# Schematic_OpenBook.net
KiCad netlist of a schematic drawn in EAGLE
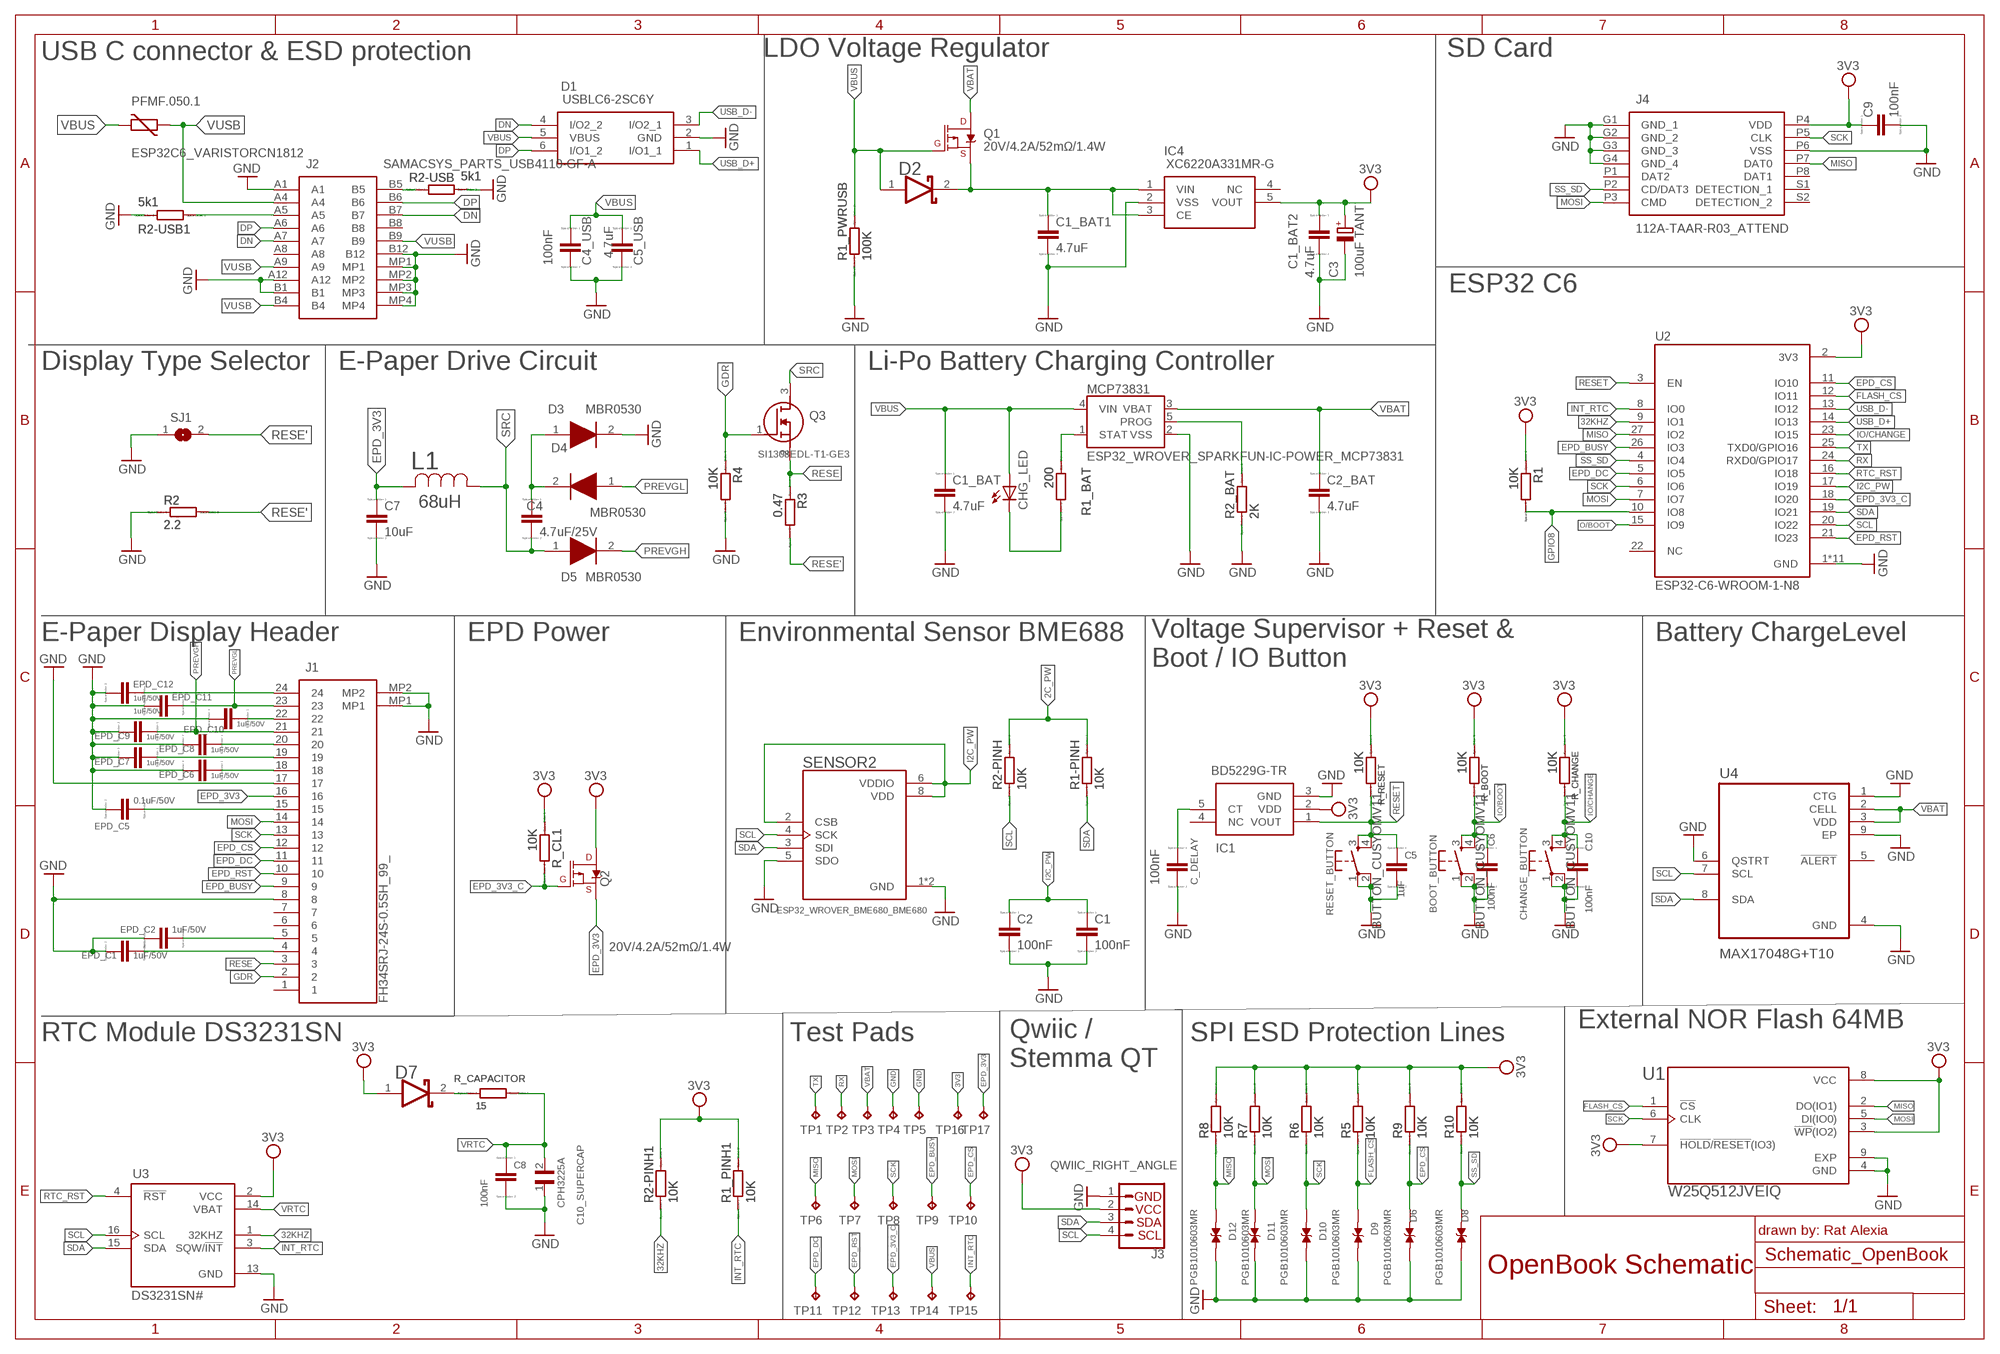
[diagram p0: schematic, sheet 1]

(export (version "E")
  (design (tool "Eeschema 10.0.6"))
  (components
    (comp (ref "BOOT_BUTTON")
      (value "BUTTON_CUSYOMV11")
      (footprint "eagle-import:MYBUTTON")
      (libsource (lib "eagle-import") (part "BUTTON_CUSYOMV11"))
    )
    (comp (ref "C1")
      (value "100nF")
      (footprint "eagle-import:ESP32_WROVER_EAGLE-LTSPICE_C0402")
      (libsource (lib "eagle-import") (part "ESP32_WROVER_EAGLE-LTSPICE_C1"))
    )
    (comp (ref "C1_BAT")
      (value "4.7uF")
      (footprint "eagle-import:ESP32_WROVER_EAGLE-LTSPICE_C0402")
      (libsource (lib "eagle-import") (part "ESP32_WROVER_EAGLE-LTSPICE_C1"))
    )
    (comp (ref "C1_BAT1")
      (value "4.7uF")
      (footprint "eagle-import:ESP32_WROVER_EAGLE-LTSPICE_C0402")
      (libsource (lib "eagle-import") (part "ESP32_WROVER_EAGLE-LTSPICE_C1"))
    )
    (comp (ref "C1_BAT2")
      (value "4.7uF")
      (footprint "eagle-import:ESP32_WROVER_EAGLE-LTSPICE_C0402")
      (libsource (lib "eagle-import") (part "ESP32_WROVER_EAGLE-LTSPICE_C1"))
    )
    (comp (ref "C2")
      (value "100nF")
      (footprint "eagle-import:ESP32_WROVER_EAGLE-LTSPICE_C0402")
      (libsource (lib "eagle-import") (part "ESP32_WROVER_EAGLE-LTSPICE_C1"))
    )
    (comp (ref "C2_BAT")
      (value "4.7uF")
      (footprint "eagle-import:ESP32_WROVER_EAGLE-LTSPICE_C0402")
      (libsource (lib "eagle-import") (part "ESP32_WROVER_EAGLE-LTSPICE_C1"))
    )
    (comp (ref "C3")
      (value "100uF TANT")
      (footprint "eagle-import:RCL_CT3528")
      (libsource (lib "eagle-import") (part "RCL_CPOL-EUCT3528"))
    )
    (comp (ref "C4")
      (value "4.7uF/25V")
      (footprint "eagle-import:ESP32_WROVER_EAGLE-LTSPICE_C0402")
      (libsource (lib "eagle-import") (part "ESP32_WROVER_EAGLE-LTSPICE_C1"))
    )
    (comp (ref "C4_USB")
      (value "100nF")
      (footprint "eagle-import:ESP32_WROVER_EAGLE-LTSPICE_C0402")
      (libsource (lib "eagle-import") (part "ESP32_WROVER_EAGLE-LTSPICE_C1"))
    )
    (comp (ref "C5")
      (value "1uF")
      (footprint "eagle-import:ESP32_WROVER_EAGLE-LTSPICE_C0402")
      (libsource (lib "eagle-import") (part "ESP32_WROVER_EAGLE-LTSPICE_C1"))
    )
    (comp (ref "C5_USB")
      (value "4.7uF")
      (footprint "eagle-import:ESP32_WROVER_EAGLE-LTSPICE_C0402")
      (libsource (lib "eagle-import") (part "ESP32_WROVER_EAGLE-LTSPICE_C1"))
    )
    (comp (ref "C6")
      (value "100nF")
      (footprint "eagle-import:ESP32_WROVER_EAGLE-LTSPICE_C0402")
      (libsource (lib "eagle-import") (part "ESP32_WROVER_EAGLE-LTSPICE_C1"))
    )
    (comp (ref "C7")
      (value "10uF")
      (footprint "eagle-import:ESP32_WROVER_EAGLE-LTSPICE_C0402")
      (libsource (lib "eagle-import") (part "ESP32_WROVER_EAGLE-LTSPICE_C1"))
    )
    (comp (ref "C8")
      (value "100nF")
      (footprint "eagle-import:ESP32_WROVER_EAGLE-LTSPICE_C0402")
      (libsource (lib "eagle-import") (part "ESP32_WROVER_EAGLE-LTSPICE_C1"))
    )
    (comp (ref "C9")
      (value "100nF")
      (footprint "eagle-import:ESP32_WROVER_EAGLE-LTSPICE_C0402")
      (libsource (lib "eagle-import") (part "ESP32_WROVER_EAGLE-LTSPICE_C1"))
    )
    (comp (ref "C10")
      (value "100nF")
      (footprint "eagle-import:ESP32_WROVER_EAGLE-LTSPICE_C0402")
      (libsource (lib "eagle-import") (part "ESP32_WROVER_EAGLE-LTSPICE_C1"))
    )
    (comp (ref "C10_SUPERCAP")
      (value "CPH3225A")
      (footprint "eagle-import:CAPCP3225X100N")
      (fields (field (name "MF") "Seiko Instruments"))
      (libsource (lib "eagle-import") (part "CPH3225A"))
    )
    (comp (ref "CHANGE_BUTTON")
      (value "BUTTON_CUSYOMV11")
      (footprint "eagle-import:MYBUTTON")
      (libsource (lib "eagle-import") (part "BUTTON_CUSYOMV11"))
    )
    (comp (ref "CHG_LED")
      (value "ADAFRUIT_LEDCHIP-LED0603")
      (footprint "eagle-import:ADAFRUIT_CHIP-LED0603")
      (libsource (lib "eagle-import") (part "ADAFRUIT_LEDCHIP-LED0603"))
    )
    (comp (ref "C_DELAY")
      (value "100nF")
      (footprint "eagle-import:ESP32_WROVER_EAGLE-LTSPICE_C0402")
      (libsource (lib "eagle-import") (part "ESP32_WROVER_EAGLE-LTSPICE_C1"))
    )
    (comp (ref "D1")
      (value "USBLC6-2SC6Y")
      (footprint "eagle-import:SOT95P280X145-6N")
      (fields (field (name "MF") "STMicroelectronics"))
      (libsource (lib "eagle-import") (part "USBLC6-2SC6Y"))
    )
    (comp (ref "D2")
      (value "ESP32_WROVER_AVX---SD0805S020S1R0_AVX_SD0805S020S1R0_0_01")
      (footprint "eagle-import:ESP32_WROVER_AVX---SD0805S020S1R0_AVX_SD0805S020S1R0_0")
      (libsource (lib "eagle-import") (part "ESP32_WROVER_AVX---SD0805S020S1R0_AVX_SD0805S020S1R0_0_01"))
    )
    (comp (ref "D3")
      (value "MBR0530")
      (footprint "eagle-import:SOD3716X135N")
      (libsource (lib "eagle-import") (part "MBR0530"))
    )
    (comp (ref "D4")
      (value "MBR0530")
      (footprint "eagle-import:SOD3716X135N")
      (libsource (lib "eagle-import") (part "MBR0530"))
    )
    (comp (ref "D5")
      (value "MBR0530")
      (footprint "eagle-import:SOD3716X135N")
      (libsource (lib "eagle-import") (part "MBR0530"))
    )
    (comp (ref "D6")
      (value "PGB1010603MR")
      (footprint "eagle-import:DIOC1608X36N")
      (libsource (lib "eagle-import") (part "PGB1010603MR"))
    )
    (comp (ref "D7")
      (value "ESP32_WROVER_AVX---SD0805S020S1R0_AVX_SD0805S020S1R0_0_01")
      (footprint "eagle-import:ESP32_WROVER_AVX---SD0805S020S1R0_AVX_SD0805S020S1R0_0")
      (libsource (lib "eagle-import") (part "ESP32_WROVER_AVX---SD0805S020S1R0_AVX_SD0805S020S1R0_0_01"))
    )
    (comp (ref "D8")
      (value "PGB1010603MR")
      (footprint "eagle-import:DIOC1608X36N")
      (libsource (lib "eagle-import") (part "PGB1010603MR"))
    )
    (comp (ref "D9")
      (value "PGB1010603MR")
      (footprint "eagle-import:DIOC1608X36N")
      (libsource (lib "eagle-import") (part "PGB1010603MR"))
    )
    (comp (ref "D10")
      (value "PGB1010603MR")
      (footprint "eagle-import:DIOC1608X36N")
      (libsource (lib "eagle-import") (part "PGB1010603MR"))
    )
    (comp (ref "D11")
      (value "PGB1010603MR")
      (footprint "eagle-import:DIOC1608X36N")
      (libsource (lib "eagle-import") (part "PGB1010603MR"))
    )
    (comp (ref "D12")
      (value "PGB1010603MR")
      (footprint "eagle-import:DIOC1608X36N")
      (libsource (lib "eagle-import") (part "PGB1010603MR"))
    )
    (comp (ref "EPD_C1")
      (value "1uF/50V")
      (footprint "eagle-import:ESP32_WROVER_EAGLE-LTSPICE_C0402")
      (libsource (lib "eagle-import") (part "ESP32_WROVER_EAGLE-LTSPICE_C1"))
    )
    (comp (ref "EPD_C2")
      (value "1uF/50V")
      (footprint "eagle-import:ESP32_WROVER_EAGLE-LTSPICE_C0402")
      (libsource (lib "eagle-import") (part "ESP32_WROVER_EAGLE-LTSPICE_C1"))
    )
    (comp (ref "EPD_C5")
      (value "0.1uF/50V")
      (footprint "eagle-import:ESP32_WROVER_EAGLE-LTSPICE_C0402")
      (libsource (lib "eagle-import") (part "ESP32_WROVER_EAGLE-LTSPICE_C1"))
    )
    (comp (ref "EPD_C6")
      (value "1uF/50V")
      (footprint "eagle-import:ESP32_WROVER_EAGLE-LTSPICE_C0402")
      (libsource (lib "eagle-import") (part "ESP32_WROVER_EAGLE-LTSPICE_C1"))
    )
    (comp (ref "EPD_C7")
      (value "1uF/50V")
      (footprint "eagle-import:ESP32_WROVER_EAGLE-LTSPICE_C0402")
      (libsource (lib "eagle-import") (part "ESP32_WROVER_EAGLE-LTSPICE_C1"))
    )
    (comp (ref "EPD_C8")
      (value "1uF/50V")
      (footprint "eagle-import:ESP32_WROVER_EAGLE-LTSPICE_C0402")
      (libsource (lib "eagle-import") (part "ESP32_WROVER_EAGLE-LTSPICE_C1"))
    )
    (comp (ref "EPD_C9")
      (value "1uF/50V")
      (footprint "eagle-import:ESP32_WROVER_EAGLE-LTSPICE_C0402")
      (libsource (lib "eagle-import") (part "ESP32_WROVER_EAGLE-LTSPICE_C1"))
    )
    (comp (ref "EPD_C10")
      (value "1uF/50V")
      (footprint "eagle-import:ESP32_WROVER_EAGLE-LTSPICE_C0402")
      (libsource (lib "eagle-import") (part "ESP32_WROVER_EAGLE-LTSPICE_C1"))
    )
    (comp (ref "EPD_C11")
      (value "1uF/50V")
      (footprint "eagle-import:ESP32_WROVER_EAGLE-LTSPICE_C0402")
      (libsource (lib "eagle-import") (part "ESP32_WROVER_EAGLE-LTSPICE_C1"))
    )
    (comp (ref "EPD_C12")
      (value "1uF/50V")
      (footprint "eagle-import:ESP32_WROVER_EAGLE-LTSPICE_C0402")
      (libsource (lib "eagle-import") (part "ESP32_WROVER_EAGLE-LTSPICE_C1"))
    )
    (comp (ref "IC1")
      (value "BD5229G-TR")
      (footprint "eagle-import:SOT95P280X125-5N")
      (fields (field (name "MOUSER_PART_NUMBER") "755-BD5229G-TR"))
      (libsource (lib "eagle-import") (part "BD5229G-TR"))
    )
    (comp (ref "IC4")
      (value "XC6220A331MR-G")
      (footprint "eagle-import:SOT95P280X120-5N")
      (fields (field (name "MOUSER_PART_NUMBER") "865-XC6220A331MR-G"))
      (libsource (lib "eagle-import") (part "XC6220A331MR-G"))
    )
    (comp (ref "J1")
      (value "FH34SRJ-24S-0.5SH_99_")
      (footprint "eagle-import:FH34SRJ24S05SH99")
      (fields
        (field (name "MANUFACTURER_PART_NUMBER") "FH34SRJ-24S-0.5SH(99)")
        (field (name "MOUSER_PART_NUMBER") "798-FH34SRJ24S05SH99")
      )
      (libsource (lib "eagle-import") (part "FH34SRJ-24S-0.5SH_99_"))
    )
    (comp (ref "J2")
      (value "SAMACSYS_PARTS_USB4110-GF-A")
      (footprint "eagle-import:SAMACSYS_PARTS_USB4110GFA")
      (fields
        (field (name "MANUFACTURER_PART_NUMBER") "USB4110-GF-A")
        (field (name "MOUSER_PART_NUMBER") "640-USB4110-GF-A")
      )
      (libsource (lib "eagle-import") (part "SAMACSYS_PARTS_USB4110-GF-A"))
    )
    (comp (ref "J3")
      (value "QWIIC_RIGHT_ANGLE")
      (footprint "eagle-import:JST04_1MM_RA")
      (libsource (lib "eagle-import") (part "QWIIC_CONNECTORJS-1MM"))
    )
    (comp (ref "J4")
      (value "112A-TAAR-R03_ATTEND")
      (footprint "eagle-import:112ATAARR03ATTEND")
      (fields (field (name "MANUFACTURER_PART_NUMBER") "112A-TAAR-R03 ATTEND"))
      (libsource (lib "eagle-import") (part "112A-TAAR-R03_ATTEND"))
    )
    (comp (ref "L1")
      (value "68uH")
      (footprint "eagle-import:IND_4828-WE-TPC_WRE")
      (fields
        (field (name "MANUFACTURER_PART_NUMBER") "744043680")
        (field (name "COPYRIGHT") "Copyright (C) 2024 Ultra Librarian. All rights reserved.")
      )
      (libsource (lib "eagle-import") (part "744043680IND_4828-WE-TPC_WRE"))
    )
    (comp (ref "MCP73831")
      (value "ESP32_WROVER_SPARKFUN-IC-POWER_MCP73831")
      (footprint "eagle-import:ESP32_WROVER_SPARKFUN-IC-POWER_SOT23-5")
      (libsource (lib "eagle-import") (part "ESP32_WROVER_SPARKFUN-IC-POWER_MCP73831"))
    )
    (comp (ref "PFMF.050.1")
      (value "ESP32C6_VARISTORCN1812")
      (footprint "eagle-import:ESP32C6_VARISTOR_CT_CN1812")
      (libsource (lib "eagle-import") (part "ESP32C6_VARISTORCN1812"))
    )
    (comp (ref "Q1")
      (value "20V/4.2A/52mΩ/1.4W")
      (footprint "eagle-import:ESP32_WROVER_SPARKFUN-DISCRETESEMI_SOT23-3")
      (libsource (lib "eagle-import") (part "ESP32_WROVER_SPARKFUN-DISCRETESEMI_MOSFET_PCH1"))
    )
    (comp (ref "Q2")
      (value "20V/4.2A/52mΩ/1.4W")
      (footprint "eagle-import:ESP32_WROVER_SPARKFUN-DISCRETESEMI_SOT23-3")
      (libsource (lib "eagle-import") (part "ESP32_WROVER_SPARKFUN-DISCRETESEMI_MOSFET_PCH1"))
    )
    (comp (ref "Q3")
      (value "SI1308EDL-T1-GE3")
      (footprint "eagle-import:SOT65P210X110-3N")
      (fields (field (name "MF") "Vishay Siliconix"))
      (libsource (lib "eagle-import") (part "SI1308EDL-T1-GE3"))
    )
    (comp (ref "R1")
      (value "10K")
      (footprint "eagle-import:ESP32_WROVER_EAGLE-LTSPICE_C0402")
      (libsource (lib "eagle-import") (part "ESP32_WROVER_EAGLE-LTSPICE_R"))
    )
    (comp (ref "R1-PINH")
      (value "10K")
      (footprint "eagle-import:ESP32_WROVER_EAGLE-LTSPICE_C0402")
      (libsource (lib "eagle-import") (part "ESP32_WROVER_EAGLE-LTSPICE_R"))
    )
    (comp (ref "R1_BAT")
      (value "200")
      (footprint "eagle-import:ESP32_WROVER_EAGLE-LTSPICE_C0402")
      (libsource (lib "eagle-import") (part "ESP32_WROVER_EAGLE-LTSPICE_R"))
    )
    (comp (ref "R1_PINH1")
      (value "10K")
      (footprint "eagle-import:ESP32_WROVER_EAGLE-LTSPICE_C0402")
      (libsource (lib "eagle-import") (part "ESP32_WROVER_EAGLE-LTSPICE_R"))
    )
    (comp (ref "R1_PWRUSB")
      (value "100K")
      (footprint "eagle-import:ESP32_WROVER_EAGLE-LTSPICE_C0402")
      (libsource (lib "eagle-import") (part "ESP32_WROVER_EAGLE-LTSPICE_R"))
    )
    (comp (ref "R2")
      (value "2.2")
      (footprint "eagle-import:ESP32_WROVER_EAGLE-LTSPICE_C0402")
      (libsource (lib "eagle-import") (part "ESP32_WROVER_EAGLE-LTSPICE_R"))
    )
    (comp (ref "R2-PINH")
      (value "10K")
      (footprint "eagle-import:ESP32_WROVER_EAGLE-LTSPICE_C0402")
      (libsource (lib "eagle-import") (part "ESP32_WROVER_EAGLE-LTSPICE_R"))
    )
    (comp (ref "R2-PINH1")
      (value "10K")
      (footprint "eagle-import:ESP32_WROVER_EAGLE-LTSPICE_C0402")
      (libsource (lib "eagle-import") (part "ESP32_WROVER_EAGLE-LTSPICE_R"))
    )
    (comp (ref "R2-USB")
      (value "5k1")
      (footprint "eagle-import:ESP32_WROVER_EAGLE-LTSPICE_C0402")
      (libsource (lib "eagle-import") (part "ESP32_WROVER_EAGLE-LTSPICE_R"))
    )
    (comp (ref "R2-USB1")
      (value "5k1")
      (footprint "eagle-import:ESP32_WROVER_EAGLE-LTSPICE_C0402")
      (libsource (lib "eagle-import") (part "ESP32_WROVER_EAGLE-LTSPICE_R"))
    )
    (comp (ref "R2_BAT")
      (value "2K")
      (footprint "eagle-import:ESP32_WROVER_EAGLE-LTSPICE_C0402")
      (libsource (lib "eagle-import") (part "ESP32_WROVER_EAGLE-LTSPICE_R"))
    )
    (comp (ref "R3")
      (value "0.47")
      (footprint "eagle-import:ESP32_WROVER_EAGLE-LTSPICE_C0402")
      (libsource (lib "eagle-import") (part "ESP32_WROVER_EAGLE-LTSPICE_R"))
    )
    (comp (ref "R4")
      (value "10K")
      (footprint "eagle-import:ESP32_WROVER_EAGLE-LTSPICE_C0402")
      (libsource (lib "eagle-import") (part "ESP32_WROVER_EAGLE-LTSPICE_R"))
    )
    (comp (ref "R5")
      (value "10K")
      (footprint "eagle-import:ESP32_WROVER_EAGLE-LTSPICE_C0402")
      (libsource (lib "eagle-import") (part "ESP32_WROVER_EAGLE-LTSPICE_R"))
    )
    (comp (ref "R6")
      (value "10K")
      (footprint "eagle-import:ESP32_WROVER_EAGLE-LTSPICE_C0402")
      (libsource (lib "eagle-import") (part "ESP32_WROVER_EAGLE-LTSPICE_R"))
    )
    (comp (ref "R7")
      (value "10K")
      (footprint "eagle-import:ESP32_WROVER_EAGLE-LTSPICE_C0402")
      (libsource (lib "eagle-import") (part "ESP32_WROVER_EAGLE-LTSPICE_R"))
    )
    (comp (ref "R8")
      (value "10K")
      (footprint "eagle-import:ESP32_WROVER_EAGLE-LTSPICE_C0402")
      (libsource (lib "eagle-import") (part "ESP32_WROVER_EAGLE-LTSPICE_R"))
    )
    (comp (ref "R9")
      (value "10K")
      (footprint "eagle-import:ESP32_WROVER_EAGLE-LTSPICE_C0402")
      (libsource (lib "eagle-import") (part "ESP32_WROVER_EAGLE-LTSPICE_R"))
    )
    (comp (ref "R10")
      (value "10K")
      (footprint "eagle-import:ESP32_WROVER_EAGLE-LTSPICE_C0402")
      (libsource (lib "eagle-import") (part "ESP32_WROVER_EAGLE-LTSPICE_R"))
    )
    (comp (ref "RESET_BUTTON")
      (value "BUTTON_CUSYOMV11")
      (footprint "eagle-import:MYBUTTON")
      (libsource (lib "eagle-import") (part "BUTTON_CUSYOMV11"))
    )
    (comp (ref "R_BOOT")
      (value "10K")
      (footprint "eagle-import:ESP32_WROVER_EAGLE-LTSPICE_C0402")
      (libsource (lib "eagle-import") (part "ESP32_WROVER_EAGLE-LTSPICE_R"))
    )
    (comp (ref "R_CAPACITOR")
      (value "15")
      (footprint "eagle-import:ESP32_WROVER_EAGLE-LTSPICE_C0402")
      (libsource (lib "eagle-import") (part "ESP32_WROVER_EAGLE-LTSPICE_R"))
    )
    (comp (ref "R_CHANGE")
      (value "10K")
      (footprint "eagle-import:ESP32_WROVER_EAGLE-LTSPICE_C0402")
      (libsource (lib "eagle-import") (part "ESP32_WROVER_EAGLE-LTSPICE_R"))
    )
    (comp (ref "R_CL1")
      (value "10K")
      (footprint "eagle-import:ESP32_WROVER_EAGLE-LTSPICE_C0402")
      (libsource (lib "eagle-import") (part "ESP32_WROVER_EAGLE-LTSPICE_R"))
    )
    (comp (ref "R_RESET")
      (value "10K")
      (footprint "eagle-import:ESP32_WROVER_EAGLE-LTSPICE_C0402")
      (libsource (lib "eagle-import") (part "ESP32_WROVER_EAGLE-LTSPICE_R"))
    )
    (comp (ref "SENSOR2")
      (value "ESP32_WROVER_BME680_BME680")
      (footprint "eagle-import:ESP32_WROVER_BME680_PSON80P300X300X100-8N")
      (fields (field (name "MF") "Bosch Sensortec") (field (name "MP") "BME680"))
      (libsource (lib "eagle-import") (part "ESP32_WROVER_BME680_BME680"))
    )
    (comp (ref "SJ1") (value "SJ") (footprint "eagle-import:SJ") (libsource (lib "eagle-import") (part "SJ")))
    (comp (ref "TP1")
      (value "TP1")
      (footprint "eagle-import:TP20R")
      (libsource (lib "eagle-import") (part "TP1"))
    )
    (comp (ref "TP2")
      (value "TP1")
      (footprint "eagle-import:TP20R")
      (libsource (lib "eagle-import") (part "TP1"))
    )
    (comp (ref "TP3")
      (value "TP1")
      (footprint "eagle-import:TP20R")
      (libsource (lib "eagle-import") (part "TP1"))
    )
    (comp (ref "TP4")
      (value "TP1")
      (footprint "eagle-import:TP20R")
      (libsource (lib "eagle-import") (part "TP1"))
    )
    (comp (ref "TP5")
      (value "TP1")
      (footprint "eagle-import:TP20R")
      (libsource (lib "eagle-import") (part "TP1"))
    )
    (comp (ref "TP6")
      (value "TP1")
      (footprint "eagle-import:TP20R")
      (libsource (lib "eagle-import") (part "TP1"))
    )
    (comp (ref "TP7")
      (value "TP1")
      (footprint "eagle-import:TP20R")
      (libsource (lib "eagle-import") (part "TP1"))
    )
    (comp (ref "TP8")
      (value "TP1")
      (footprint "eagle-import:TP20R")
      (libsource (lib "eagle-import") (part "TP1"))
    )
    (comp (ref "TP9")
      (value "TP1")
      (footprint "eagle-import:TP20R")
      (libsource (lib "eagle-import") (part "TP1"))
    )
    (comp (ref "TP10")
      (value "TP1")
      (footprint "eagle-import:TP20R")
      (libsource (lib "eagle-import") (part "TP1"))
    )
    (comp (ref "TP11")
      (value "TP1")
      (footprint "eagle-import:TP20R")
      (libsource (lib "eagle-import") (part "TP1"))
    )
    (comp (ref "TP12")
      (value "TP1")
      (footprint "eagle-import:TP20R")
      (libsource (lib "eagle-import") (part "TP1"))
    )
    (comp (ref "TP13")
      (value "TP1")
      (footprint "eagle-import:TP20R")
      (libsource (lib "eagle-import") (part "TP1"))
    )
    (comp (ref "TP14")
      (value "TP1")
      (footprint "eagle-import:TP20R")
      (libsource (lib "eagle-import") (part "TP1"))
    )
    (comp (ref "TP15")
      (value "TP1")
      (footprint "eagle-import:TP20R")
      (libsource (lib "eagle-import") (part "TP1"))
    )
    (comp (ref "TP16")
      (value "TP1")
      (footprint "eagle-import:TP20R")
      (libsource (lib "eagle-import") (part "TP1"))
    )
    (comp (ref "TP17")
      (value "TP1")
      (footprint "eagle-import:TP20R")
      (libsource (lib "eagle-import") (part "TP1"))
    )
    (comp (ref "U1")
      (value "W25Q512JVEIQ")
      (footprint "eagle-import:SON127P600X800X80-9N")
      (fields (field (name "MF") "Winbond Electronics"))
      (libsource (lib "eagle-import") (part "W25Q512JVEIQ"))
    )
    (comp (ref "U2")
      (value "ESP32-C6-WROOM-1-N8")
      (footprint "eagle-import:XCVR_ESP32-C6-WROOM-1-N8")
      (fields (field (name "MF") "Espressif Systems"))
      (libsource (lib "eagle-import") (part "ESP32-C6-WROOM-1-N8"))
    )
    (comp (ref "U3")
      (value "DS3231SN#")
      (footprint "eagle-import:SOIC127P1032X265-16N")
      (fields (field (name "MF") "Analog Devices"))
      (libsource (lib "eagle-import") (part "DS3231SN#"))
    )
    (comp (ref "U4")
      (value "MAX17048G+T10")
      (footprint "eagle-import:SON50P200X200X80-9N")
      (fields (field (name "MF") "Analog Devices"))
      (libsource (lib "eagle-import") (part "MAX17048G+T10"))
    )
  )
  (nets
    (net (code "1") (name "2C_PW") (class "Default")
      (node (ref "R1-PINH") (pin "2") (pinfunction "2_2") (pintype "passive"))
      (node (ref "R2-PINH") (pin "2") (pinfunction "2_2") (pintype "passive"))
    )
    (net (code "2") (name "3V3") (class "Default")
      (node (ref "C1_BAT2") (pin "1") (pinfunction "1_1") (pintype "passive"))
      (node (ref "C3") (pin "+") (pinfunction "+_+") (pintype "passive"))
      (node (ref "C9") (pin "1") (pinfunction "1_1") (pintype "passive"))
      (node (ref "D7") (pin "1") (pinfunction "ANODE_1") (pintype "bidirectional"))
      (node (ref "IC1") (pin "2") (pinfunction "VDD_2") (pintype "bidirectional"))
      (node (ref "IC4") (pin "5") (pinfunction "VOUT_5") (pintype "bidirectional"))
      (node (ref "J3") (pin "2") (pinfunction "2_2") (pintype "power_in"))
      (node (ref "J4") (pin "P4") (pinfunction "VDD_P4") (pintype "bidirectional"))
      (node (ref "Q2") (pin "1") (pinfunction "D_1") (pintype "bidirectional"))
      (node (ref "R1") (pin "1") (pinfunction "1_1") (pintype "passive"))
      (node (ref "R10") (pin "2") (pinfunction "2_2") (pintype "passive"))
      (node (ref "R1_PINH1") (pin "2") (pinfunction "2_2") (pintype "passive"))
      (node (ref "R2-PINH1") (pin "2") (pinfunction "2_2") (pintype "passive"))
      (node (ref "R5") (pin "2") (pinfunction "2_2") (pintype "passive"))
      (node (ref "R6") (pin "2") (pinfunction "2_2") (pintype "passive"))
      (node (ref "R7") (pin "2") (pinfunction "2_2") (pintype "passive"))
      (node (ref "R8") (pin "2") (pinfunction "2_2") (pintype "passive"))
      (node (ref "R9") (pin "2") (pinfunction "2_2") (pintype "passive"))
      (node (ref "R_BOOT") (pin "1") (pinfunction "1_1") (pintype "passive"))
      (node (ref "R_CHANGE") (pin "1") (pinfunction "1_1") (pintype "passive"))
      (node (ref "R_CL1") (pin "1") (pinfunction "1_1") (pintype "passive"))
      (node (ref "R_RESET") (pin "1") (pinfunction "1_1") (pintype "passive"))
      (node (ref "TP16") (pin "TP") (pinfunction "TP_TP") (pintype "input"))
      (node (ref "U1") (pin "3") (pinfunction "~{WP}(IO2)_3") (pintype "bidirectional"))
      (node (ref "U1") (pin "7") (pinfunction "~{HOLD}/~{RESET}(IO3)_7") (pintype "bidirectional"))
      (node (ref "U1") (pin "8") (pinfunction "VCC_8") (pintype "power_in"))
      (node (ref "U2") (pin "2") (pinfunction "3V3_2") (pintype "power_in"))
      (node (ref "U3") (pin "2") (pinfunction "VCC_2") (pintype "power_in"))
    )
    (net (code "3") (name "32KHZ") (class "Default")
      (node (ref "R2-PINH1") (pin "1") (pinfunction "1_1") (pintype "passive"))
      (node (ref "U2") (pin "9") (pinfunction "IO1_9") (pintype "bidirectional"))
      (node (ref "U3") (pin "1") (pinfunction "32KHZ_1") (pintype "output"))
    )
    (net (code "4") (name "DN") (class "Default")
      (node (ref "D1") (pin "4") (pinfunction "I/O2_2_4") (pintype "bidirectional"))
      (node (ref "J2") (pin "A7") (pinfunction "A7_A7") (pintype "bidirectional"))
      (node (ref "J2") (pin "B7") (pinfunction "B7_B7") (pintype "bidirectional"))
    )
    (net (code "5") (name "DP") (class "Default")
      (node (ref "D1") (pin "6") (pinfunction "I/O1_2_6") (pintype "bidirectional"))
      (node (ref "J2") (pin "A6") (pinfunction "A6_A6") (pintype "bidirectional"))
      (node (ref "J2") (pin "B6") (pinfunction "B6_B6") (pintype "bidirectional"))
    )
    (net (code "6") (name "EPD_3V3") (class "Default")
      (node (ref "C7") (pin "1") (pinfunction "1_1") (pintype "passive"))
      (node (ref "J1") (pin "16") (pinfunction "16_16") (pintype "bidirectional"))
      (node (ref "L1") (pin "2") (pinfunction "2_2") (pintype "passive"))
      (node (ref "Q2") (pin "3") (pinfunction "S_3") (pintype "bidirectional"))
      (node (ref "TP17") (pin "TP") (pinfunction "TP_TP") (pintype "input"))
    )
    (net (code "7") (name "EPD_3V3_C") (class "Default")
      (node (ref "Q2") (pin "2") (pinfunction "G_2") (pintype "bidirectional"))
      (node (ref "R_CL1") (pin "2") (pinfunction "2_2") (pintype "passive"))
      (node (ref "TP13") (pin "TP") (pinfunction "TP_TP") (pintype "input"))
      (node (ref "U2") (pin "18") (pinfunction "IO20_18") (pintype "bidirectional"))
    )
    (net (code "8") (name "EPD_BUSY") (class "Default")
      (node (ref "J1") (pin "9") (pinfunction "9_9") (pintype "bidirectional"))
      (node (ref "TP9") (pin "TP") (pinfunction "TP_TP") (pintype "input"))
      (node (ref "U2") (pin "26") (pinfunction "IO3_26") (pintype "bidirectional"))
    )
    (net (code "9") (name "EPD_CS") (class "Default")
      (node (ref "D6") (pin "1") (pinfunction "1_1") (pintype "passive"))
      (node (ref "J1") (pin "12") (pinfunction "12_12") (pintype "bidirectional"))
      (node (ref "R9") (pin "1") (pinfunction "1_1") (pintype "passive"))
      (node (ref "TP10") (pin "TP") (pinfunction "TP_TP") (pintype "input"))
      (node (ref "U2") (pin "11") (pinfunction "IO10_11") (pintype "bidirectional"))
    )
    (net (code "10") (name "EPD_DC") (class "Default")
      (node (ref "J1") (pin "11") (pinfunction "11_11") (pintype "bidirectional"))
      (node (ref "TP11") (pin "TP") (pinfunction "TP_TP") (pintype "input"))
      (node (ref "U2") (pin "5") (pinfunction "IO5_5") (pintype "bidirectional"))
    )
    (net (code "11") (name "EPD_RST") (class "Default")
      (node (ref "J1") (pin "10") (pinfunction "10_10") (pintype "bidirectional"))
      (node (ref "TP12") (pin "TP") (pinfunction "TP_TP") (pintype "input"))
      (node (ref "U2") (pin "21") (pinfunction "IO23_21") (pintype "bidirectional"))
    )
    (net (code "12") (name "FLASH_CS") (class "Default")
      (node (ref "D9") (pin "1") (pinfunction "1_1") (pintype "passive"))
      (node (ref "R5") (pin "1") (pinfunction "1_1") (pintype "passive"))
      (node (ref "U1") (pin "1") (pinfunction "~{CS}_1") (pintype "input"))
      (node (ref "U2") (pin "12") (pinfunction "IO11_12") (pintype "bidirectional"))
    )
    (net (code "13") (name "GDR") (class "Default")
      (node (ref "J1") (pin "2") (pinfunction "2_2") (pintype "bidirectional"))
      (node (ref "Q3") (pin "1") (pinfunction "G_1") (pintype "bidirectional"))
      (node (ref "R4") (pin "1") (pinfunction "1_1") (pintype "passive"))
    )
    (net (code "14") (name "GND") (class "Default")
      (node (ref "BOOT_BUTTON") (pin "1") (pinfunction "1_1") (pintype "passive"))
      (node (ref "BOOT_BUTTON") (pin "2") (pinfunction "2_2") (pintype "passive"))
      (node (ref "C1") (pin "2") (pinfunction "2_2") (pintype "passive"))
      (node (ref "C10") (pin "2") (pinfunction "2_2") (pintype "passive"))
      (node (ref "C10_SUPERCAP") (pin "1") (pinfunction "1_1") (pintype "passive"))
      (node (ref "C1_BAT") (pin "2") (pinfunction "2_2") (pintype "passive"))
      (node (ref "C1_BAT1") (pin "2") (pinfunction "2_2") (pintype "passive"))
      (node (ref "C1_BAT2") (pin "2") (pinfunction "2_2") (pintype "passive"))
      (node (ref "C2") (pin "2") (pinfunction "2_2") (pintype "passive"))
      (node (ref "C2_BAT") (pin "2") (pinfunction "2_2") (pintype "passive"))
      (node (ref "C3") (pin "-") (pinfunction "-_-") (pintype "passive"))
      (node (ref "C4_USB") (pin "2") (pinfunction "2_2") (pintype "passive"))
      (node (ref "C5") (pin "2") (pinfunction "2_2") (pintype "passive"))
      (node (ref "C5_USB") (pin "2") (pinfunction "2_2") (pintype "passive"))
      (node (ref "C6") (pin "2") (pinfunction "2_2") (pintype "passive"))
      (node (ref "C7") (pin "2") (pinfunction "2_2") (pintype "passive"))
      (node (ref "C8") (pin "2") (pinfunction "2_2") (pintype "passive"))
      (node (ref "C9") (pin "2") (pinfunction "2_2") (pintype "passive"))
      (node (ref "CHANGE_BUTTON") (pin "1") (pinfunction "1_1") (pintype "passive"))
      (node (ref "CHANGE_BUTTON") (pin "2") (pinfunction "2_2") (pintype "passive"))
      (node (ref "C_DELAY") (pin "2") (pinfunction "2_2") (pintype "passive"))
      (node (ref "D1") (pin "2") (pinfunction "GND_2") (pintype "bidirectional"))
      (node (ref "D10") (pin "2") (pinfunction "2_2") (pintype "passive"))
      (node (ref "D11") (pin "2") (pinfunction "2_2") (pintype "passive"))
      (node (ref "D12") (pin "2") (pinfunction "2_2") (pintype "passive"))
      (node (ref "D3") (pin "2") (pinfunction "K_2") (pintype "bidirectional"))
      (node (ref "D6") (pin "2") (pinfunction "2_2") (pintype "passive"))
      (node (ref "D8") (pin "2") (pinfunction "2_2") (pintype "passive"))
      (node (ref "D9") (pin "2") (pinfunction "2_2") (pintype "passive"))
      (node (ref "EPD_C1") (pin "2") (pinfunction "2_2") (pintype "passive"))
      (node (ref "EPD_C10") (pin "2") (pinfunction "2_2") (pintype "passive"))
      (node (ref "EPD_C11") (pin "2") (pinfunction "2_2") (pintype "passive"))
      (node (ref "EPD_C12") (pin "2") (pinfunction "2_2") (pintype "passive"))
      (node (ref "EPD_C2") (pin "2") (pinfunction "2_2") (pintype "passive"))
      (node (ref "EPD_C5") (pin "2") (pinfunction "2_2") (pintype "passive"))
      (node (ref "EPD_C6") (pin "2") (pinfunction "2_2") (pintype "passive"))
      (node (ref "EPD_C7") (pin "2") (pinfunction "2_2") (pintype "passive"))
      (node (ref "EPD_C8") (pin "2") (pinfunction "2_2") (pintype "passive"))
      (node (ref "EPD_C9") (pin "2") (pinfunction "2_2") (pintype "passive"))
      (node (ref "IC1") (pin "3") (pinfunction "GND_3") (pintype "bidirectional"))
      (node (ref "IC4") (pin "2") (pinfunction "VSS_2") (pintype "bidirectional"))
      (node (ref "J1") (pin "17") (pinfunction "17_17") (pintype "bidirectional"))
      (node (ref "J1") (pin "8") (pinfunction "8_8") (pintype "bidirectional"))
      (node (ref "J1") (pin "MP1") (pinfunction "MP1_MP1") (pintype "bidirectional"))
      (node (ref "J1") (pin "MP2") (pinfunction "MP2_MP2") (pintype "bidirectional"))
      (node (ref "J2") (pin "A1") (pinfunction "A1_A1") (pintype "bidirectional"))
      (node (ref "J2") (pin "A12") (pinfunction "A12_A12") (pintype "bidirectional"))
      (node (ref "J2") (pin "B1") (pinfunction "B1_B1") (pintype "bidirectional"))
      (node (ref "J2") (pin "B12") (pinfunction "B12_B12") (pintype "bidirectional"))
      (node (ref "J2") (pin "MP1") (pinfunction "MP1_MP1") (pintype "bidirectional"))
      (node (ref "J2") (pin "MP2") (pinfunction "MP2_MP2") (pintype "bidirectional"))
      (node (ref "J2") (pin "MP3") (pinfunction "MP3_MP3") (pintype "bidirectional"))
      (node (ref "J2") (pin "MP4") (pinfunction "MP4_MP4") (pintype "bidirectional"))
      (node (ref "J3") (pin "1") (pinfunction "1_1") (pintype "power_in"))
      (node (ref "J4") (pin "G1") (pinfunction "GND_1_G1") (pintype "bidirectional"))
      (node (ref "J4") (pin "G2") (pinfunction "GND_2_G2") (pintype "bidirectional"))
      (node (ref "J4") (pin "G3") (pinfunction "GND_3_G3") (pintype "bidirectional"))
      (node (ref "J4") (pin "G4") (pinfunction "GND_4_G4") (pintype "bidirectional"))
      (node (ref "J4") (pin "P6") (pinfunction "VSS_P6") (pintype "bidirectional"))
      (node (ref "MCP73831") (pin "2") (pinfunction "VSS_2") (pintype "power_in"))
      (node (ref "R1_PWRUSB") (pin "1") (pinfunction "1_1") (pintype "passive"))
      (node (ref "R2") (pin "1") (pinfunction "1_1") (pintype "passive"))
      (node (ref "R2-USB") (pin "2") (pinfunction "2_2") (pintype "passive"))
      (node (ref "R2-USB1") (pin "1") (pinfunction "1_1") (pintype "passive"))
      (node (ref "R2_BAT") (pin "1") (pinfunction "1_1") (pintype "passive"))
      (node (ref "R4") (pin "2") (pinfunction "2_2") (pintype "passive"))
      (node (ref "RESET_BUTTON") (pin "1") (pinfunction "1_1") (pintype "passive"))
      (node (ref "RESET_BUTTON") (pin "2") (pinfunction "2_2") (pintype "passive"))
      (node (ref "SENSOR2") (pin "1") (pinfunction "GND_1") (pintype "power_in"))
      (node (ref "SENSOR2") (pin "5") (pinfunction "SDO_5") (pintype "bidirectional"))
      (node (ref "SENSOR2") (pin "7") (pinfunction "GND_7") (pintype "power_in"))
      (node (ref "SJ1") (pin "1") (pinfunction "1_1") (pintype "passive"))
      (node (ref "TP4") (pin "TP") (pinfunction "TP_TP") (pintype "input"))
      (node (ref "TP5") (pin "TP") (pinfunction "TP_TP") (pintype "input"))
      (node (ref "U1") (pin "4") (pinfunction "GND_4") (pintype "power_in"))
      (node (ref "U1") (pin "9") (pinfunction "EXP_9") (pintype "passive"))
      (node (ref "U2") (pin "1") (pinfunction "GND_1") (pintype "power_in"))
      (node (ref "U2") (pin "28") (pinfunction "GND_28") (pintype "power_in"))
      (node (ref "U2") (pin "29_1") (pinfunction "GND_29_1") (pintype "power_in"))
      (node (ref "U2") (pin "29_2") (pinfunction "GND_29_2") (pintype "power_in"))
      (node (ref "U2") (pin "29_3") (pinfunction "GND_29_3") (pintype "power_in"))
      (node (ref "U2") (pin "29_4") (pinfunction "GND_29_4") (pintype "power_in"))
      (node (ref "U2") (pin "29_5") (pinfunction "GND_29_5") (pintype "power_in"))
      (node (ref "U2") (pin "29_6") (pinfunction "GND_29_6") (pintype "power_in"))
      (node (ref "U2") (pin "29_7") (pinfunction "GND_29_7") (pintype "power_in"))
      (node (ref "U2") (pin "29_8") (pinfunction "GND_29_8") (pintype "power_in"))
      (node (ref "U2") (pin "29_9") (pinfunction "GND_29_9") (pintype "power_in"))
      (node (ref "U3") (pin "13") (pinfunction "GND_13") (pintype "power_in"))
      (node (ref "U4") (pin "1") (pinfunction "CTG_1") (pintype "power_in"))
      (node (ref "U4") (pin "4") (pinfunction "GND_4") (pintype "power_in"))
      (node (ref "U4") (pin "6") (pinfunction "QSTRT_6") (pintype "input"))
      (node (ref "U4") (pin "9") (pinfunction "EP_9") (pintype "power_in"))
    )
    (net (code "15") (name "GPIO8") (class "Default")
      (node (ref "R1") (pin "2") (pinfunction "2_2") (pintype "passive"))
      (node (ref "U2") (pin "10") (pinfunction "IO8_10") (pintype "bidirectional"))
    )
    (net (code "16") (name "I2C_PW") (class "Default")
      (node (ref "C1") (pin "1") (pinfunction "1_1") (pintype "passive"))
      (node (ref "C2") (pin "1") (pinfunction "1_1") (pintype "passive"))
      (node (ref "SENSOR2") (pin "2") (pinfunction "CSB_2") (pintype "input"))
      (node (ref "SENSOR2") (pin "6") (pinfunction "VDDIO_6") (pintype "power_in"))
      (node (ref "SENSOR2") (pin "8") (pinfunction "VDD_8") (pintype "power_in"))
      (node (ref "U2") (pin "17") (pinfunction "IO19_17") (pintype "bidirectional"))
    )
    (net (code "17") (name "INT_RTC") (class "Default")
      (node (ref "R1_PINH1") (pin "1") (pinfunction "1_1") (pintype "passive"))
      (node (ref "TP15") (pin "TP") (pinfunction "TP_TP") (pintype "input"))
      (node (ref "U2") (pin "8") (pinfunction "IO0_8") (pintype "bidirectional"))
      (node (ref "U3") (pin "3") (pinfunction "SQW/~{INT}_3") (pintype "output"))
    )
    (net (code "18") (name "IO{slash}BOOT") (class "Default")
      (node (ref "BOOT_BUTTON") (pin "3") (pinfunction "3_3") (pintype "passive"))
      (node (ref "BOOT_BUTTON") (pin "4") (pinfunction "4_4") (pintype "passive"))
      (node (ref "C6") (pin "1") (pinfunction "1_1") (pintype "passive"))
      (node (ref "R_BOOT") (pin "2") (pinfunction "2_2") (pintype "passive"))
      (node (ref "U2") (pin "15") (pinfunction "IO9_15") (pintype "bidirectional"))
    )
    (net (code "19") (name "IO{slash}CHANGE") (class "Default")
      (node (ref "C10") (pin "1") (pinfunction "1_1") (pintype "passive"))
      (node (ref "CHANGE_BUTTON") (pin "3") (pinfunction "3_3") (pintype "passive"))
      (node (ref "CHANGE_BUTTON") (pin "4") (pinfunction "4_4") (pintype "passive"))
      (node (ref "R_CHANGE") (pin "2") (pinfunction "2_2") (pintype "passive"))
      (node (ref "U2") (pin "23") (pinfunction "IO15_23") (pintype "bidirectional"))
    )
    (net (code "20") (name "MISO") (class "Default")
      (node (ref "D12") (pin "1") (pinfunction "1_1") (pintype "passive"))
      (node (ref "J4") (pin "P7") (pinfunction "DAT0_P7") (pintype "bidirectional"))
      (node (ref "R8") (pin "1") (pinfunction "1_1") (pintype "passive"))
      (node (ref "TP6") (pin "TP") (pinfunction "TP_TP") (pintype "input"))
      (node (ref "U1") (pin "2") (pinfunction "DO(IO1)_2") (pintype "bidirectional"))
      (node (ref "U2") (pin "27") (pinfunction "IO2_27") (pintype "bidirectional"))
    )
    (net (code "21") (name "MOSI") (class "Default")
      (node (ref "D11") (pin "1") (pinfunction "1_1") (pintype "passive"))
      (node (ref "J1") (pin "14") (pinfunction "14_14") (pintype "bidirectional"))
      (node (ref "J4") (pin "P3") (pinfunction "CMD_P3") (pintype "bidirectional"))
      (node (ref "R7") (pin "1") (pinfunction "1_1") (pintype "passive"))
      (node (ref "TP7") (pin "TP") (pinfunction "TP_TP") (pintype "input"))
      (node (ref "U1") (pin "5") (pinfunction "DI(IO0)_5") (pintype "bidirectional"))
      (node (ref "U2") (pin "7") (pinfunction "IO7_7") (pintype "bidirectional"))
    )
    (net (code "22") (name "Net-(CHG_LED-PadC)") (class "Default")
      (node (ref "CHG_LED") (pin "C") (pinfunction "C_C") (pintype "passive"))
      (node (ref "R1_BAT") (pin "2") (pinfunction "2_2") (pintype "passive"))
    )
    (net (code "23") (name "Net-(D2-CATHODE)") (class "Default")
      (node (ref "C1_BAT1") (pin "1") (pinfunction "1_1") (pintype "passive"))
      (node (ref "D2") (pin "2") (pinfunction "CATHODE_2") (pintype "bidirectional"))
      (node (ref "IC4") (pin "1") (pinfunction "VIN_1") (pintype "bidirectional"))
      (node (ref "IC4") (pin "3") (pinfunction "CE_3") (pintype "bidirectional"))
      (node (ref "Q1") (pin "3") (pinfunction "S_3") (pintype "bidirectional"))
    )
    (net (code "24") (name "Net-(D3-A)") (class "Default")
      (node (ref "C4") (pin "1") (pinfunction "1_1") (pintype "passive"))
      (node (ref "D3") (pin "1") (pinfunction "A_1") (pintype "bidirectional"))
      (node (ref "D4") (pin "2") (pinfunction "K_2") (pintype "bidirectional"))
    )
    (net (code "25") (name "Net-(D7-CATHODE)") (class "Default")
      (node (ref "D7") (pin "2") (pinfunction "CATHODE_2") (pintype "bidirectional"))
      (node (ref "R_CAPACITOR") (pin "2") (pinfunction "2_2") (pintype "passive"))
    )
    (net (code "26") (name "Net-(EPD_C1-Pad1)") (class "Default")
      (node (ref "EPD_C1") (pin "1") (pinfunction "1_1") (pintype "passive"))
      (node (ref "J1") (pin "4") (pinfunction "4_4") (pintype "bidirectional"))
    )
    (net (code "27") (name "Net-(EPD_C2-Pad1)") (class "Default")
      (node (ref "EPD_C2") (pin "1") (pinfunction "1_1") (pintype "passive"))
      (node (ref "J1") (pin "5") (pinfunction "5_5") (pintype "bidirectional"))
    )
    (net (code "28") (name "Net-(EPD_C5-Pad1)") (class "Default")
      (node (ref "EPD_C5") (pin "1") (pinfunction "1_1") (pintype "passive"))
      (node (ref "J1") (pin "15") (pinfunction "15_15") (pintype "bidirectional"))
    )
    (net (code "29") (name "Net-(EPD_C6-Pad1)") (class "Default")
      (node (ref "EPD_C6") (pin "1") (pinfunction "1_1") (pintype "passive"))
      (node (ref "J1") (pin "18") (pinfunction "18_18") (pintype "bidirectional"))
    )
    (net (code "30") (name "Net-(EPD_C7-Pad1)") (class "Default")
      (node (ref "EPD_C7") (pin "1") (pinfunction "1_1") (pintype "passive"))
      (node (ref "J1") (pin "19") (pinfunction "19_19") (pintype "bidirectional"))
    )
    (net (code "31") (name "Net-(EPD_C8-Pad1)") (class "Default")
      (node (ref "EPD_C8") (pin "1") (pinfunction "1_1") (pintype "passive"))
      (node (ref "J1") (pin "20") (pinfunction "20_20") (pintype "bidirectional"))
    )
    (net (code "32") (name "Net-(EPD_C10-Pad1)") (class "Default")
      (node (ref "EPD_C10") (pin "1") (pinfunction "1_1") (pintype "passive"))
      (node (ref "J1") (pin "22") (pinfunction "22_22") (pintype "bidirectional"))
    )
    (net (code "33") (name "Net-(EPD_C12-Pad1)") (class "Default")
      (node (ref "EPD_C12") (pin "1") (pinfunction "1_1") (pintype "passive"))
      (node (ref "J1") (pin "24") (pinfunction "24_24") (pintype "bidirectional"))
    )
    (net (code "34") (name "Net-(IC1-CT)") (class "Default")
      (node (ref "C_DELAY") (pin "1") (pinfunction "1_1") (pintype "passive"))
      (node (ref "IC1") (pin "5") (pinfunction "CT_5") (pintype "bidirectional"))
    )
    (net (code "35") (name "Net-(J2-PadA5)") (class "Default")
      (node (ref "J2") (pin "A5") (pinfunction "A5_A5") (pintype "bidirectional"))
      (node (ref "R2-USB1") (pin "2") (pinfunction "2_2") (pintype "passive"))
    )
    (net (code "36") (name "Net-(J2-PadB5)") (class "Default")
      (node (ref "J2") (pin "B5") (pinfunction "B5_B5") (pintype "bidirectional"))
      (node (ref "R2-USB") (pin "1") (pinfunction "1_1") (pintype "passive"))
    )
    (net (code "37") (name "Net-(MCP73831-PROG)") (class "Default")
      (node (ref "MCP73831") (pin "5") (pinfunction "PROG_5") (pintype "input"))
      (node (ref "R2_BAT") (pin "2") (pinfunction "2_2") (pintype "passive"))
    )
    (net (code "38") (name "Net-(MCP73831-STAT)") (class "Default")
      (node (ref "MCP73831") (pin "1") (pinfunction "STAT_1") (pintype "output"))
      (node (ref "R1_BAT") (pin "1") (pinfunction "1_1") (pintype "passive"))
    )
    (net (code "39") (name "PREVGH") (class "Default")
      (node (ref "D5") (pin "2") (pinfunction "K_2") (pintype "bidirectional"))
      (node (ref "EPD_C9") (pin "1") (pinfunction "1_1") (pintype "passive"))
      (node (ref "J1") (pin "21") (pinfunction "21_21") (pintype "bidirectional"))
    )
    (net (code "40") (name "PREVGL") (class "Default")
      (node (ref "D4") (pin "1") (pinfunction "A_1") (pintype "bidirectional"))
      (node (ref "EPD_C11") (pin "1") (pinfunction "1_1") (pintype "passive"))
      (node (ref "J1") (pin "23") (pinfunction "23_23") (pintype "bidirectional"))
    )
    (net (code "41") (name "RESE") (class "Default")
      (node (ref "J1") (pin "3") (pinfunction "3_3") (pintype "bidirectional"))
      (node (ref "Q3") (pin "2") (pinfunction "S_2") (pintype "bidirectional"))
      (node (ref "R3") (pin "1") (pinfunction "1_1") (pintype "passive"))
    )
    (net (code "42") (name "RESE'") (class "Default")
      (node (ref "R2") (pin "2") (pinfunction "2_2") (pintype "passive"))
      (node (ref "R3") (pin "2") (pinfunction "2_2") (pintype "passive"))
      (node (ref "SJ1") (pin "2") (pinfunction "2_2") (pintype "passive"))
    )
    (net (code "43") (name "RESET") (class "Default")
      (node (ref "C5") (pin "1") (pinfunction "1_1") (pintype "passive"))
      (node (ref "IC1") (pin "1") (pinfunction "VOUT_1") (pintype "bidirectional"))
      (node (ref "RESET_BUTTON") (pin "3") (pinfunction "3_3") (pintype "passive"))
      (node (ref "RESET_BUTTON") (pin "4") (pinfunction "4_4") (pintype "passive"))
      (node (ref "R_RESET") (pin "2") (pinfunction "2_2") (pintype "passive"))
      (node (ref "U2") (pin "3") (pinfunction "EN_3") (pintype "input"))
    )
    (net (code "44") (name "RTC_RST") (class "Default")
      (node (ref "U2") (pin "16") (pinfunction "IO18_16") (pintype "bidirectional"))
      (node (ref "U3") (pin "4") (pinfunction "~{RST}_4") (pintype "input"))
    )
    (net (code "45") (name "RX") (class "Default")
      (node (ref "TP2") (pin "TP") (pinfunction "TP_TP") (pintype "input"))
      (node (ref "U2") (pin "24") (pinfunction "RXD0/GPIO17_24") (pintype "bidirectional"))
    )
    (net (code "46") (name "SCK") (class "Default")
      (node (ref "D10") (pin "1") (pinfunction "1_1") (pintype "passive"))
      (node (ref "J1") (pin "13") (pinfunction "13_13") (pintype "bidirectional"))
      (node (ref "J4") (pin "P5") (pinfunction "CLK_P5") (pintype "bidirectional"))
      (node (ref "R6") (pin "1") (pinfunction "1_1") (pintype "passive"))
      (node (ref "TP8") (pin "TP") (pinfunction "TP_TP") (pintype "input"))
      (node (ref "U1") (pin "6") (pinfunction "CLK_6") (pintype "input"))
      (node (ref "U2") (pin "6") (pinfunction "IO6_6") (pintype "bidirectional"))
    )
    (net (code "47") (name "SCL") (class "Default")
      (node (ref "J3") (pin "4") (pinfunction "4_4") (pintype "passive"))
      (node (ref "R2-PINH") (pin "1") (pinfunction "1_1") (pintype "passive"))
      (node (ref "SENSOR2") (pin "4") (pinfunction "SCK_4") (pintype "input"))
      (node (ref "U2") (pin "20") (pinfunction "IO22_20") (pintype "bidirectional"))
      (node (ref "U3") (pin "16") (pinfunction "SCL_16") (pintype "input"))
      (node (ref "U4") (pin "7") (pinfunction "SCL_7") (pintype "input"))
    )
    (net (code "48") (name "SDA") (class "Default")
      (node (ref "J3") (pin "3") (pinfunction "3_3") (pintype "passive"))
      (node (ref "R1-PINH") (pin "1") (pinfunction "1_1") (pintype "passive"))
      (node (ref "SENSOR2") (pin "3") (pinfunction "SDI_3") (pintype "bidirectional"))
      (node (ref "U2") (pin "19") (pinfunction "IO21_19") (pintype "bidirectional"))
      (node (ref "U3") (pin "15") (pinfunction "SDA_15") (pintype "bidirectional"))
      (node (ref "U4") (pin "8") (pinfunction "SDA_8") (pintype "bidirectional"))
    )
    (net (code "49") (name "SRC") (class "Default")
      (node (ref "C4") (pin "2") (pinfunction "2_2") (pintype "passive"))
      (node (ref "D5") (pin "1") (pinfunction "A_1") (pintype "bidirectional"))
      (node (ref "L1") (pin "1") (pinfunction "1_1") (pintype "passive"))
      (node (ref "Q3") (pin "3") (pinfunction "D_3") (pintype "bidirectional"))
    )
    (net (code "50") (name "SS_SD") (class "Default")
      (node (ref "D8") (pin "1") (pinfunction "1_1") (pintype "passive"))
      (node (ref "J4") (pin "P2") (pinfunction "CD/DAT3_P2") (pintype "bidirectional"))
      (node (ref "R10") (pin "1") (pinfunction "1_1") (pintype "passive"))
      (node (ref "U2") (pin "4") (pinfunction "IO4_4") (pintype "bidirectional"))
    )
    (net (code "51") (name "TX") (class "Default")
      (node (ref "TP1") (pin "TP") (pinfunction "TP_TP") (pintype "input"))
      (node (ref "U2") (pin "25") (pinfunction "TXD0/GPIO16_25") (pintype "bidirectional"))
    )
    (net (code "52") (name "USB_D+") (class "Default")
      (node (ref "D1") (pin "1") (pinfunction "I/O1_1_1") (pintype "bidirectional"))
      (node (ref "U2") (pin "14") (pinfunction "IO13_14") (pintype "bidirectional"))
    )
    (net (code "53") (name "USB_D-") (class "Default")
      (node (ref "D1") (pin "3") (pinfunction "I/O2_1_3") (pintype "bidirectional"))
      (node (ref "U2") (pin "13") (pinfunction "IO12_13") (pintype "bidirectional"))
    )
    (net (code "54") (name "VBAT") (class "Default")
      (node (ref "C2_BAT") (pin "1") (pinfunction "1_1") (pintype "passive"))
      (node (ref "MCP73831") (pin "3") (pinfunction "VBAT_3") (pintype "power_in"))
      (node (ref "Q1") (pin "1") (pinfunction "D_1") (pintype "bidirectional"))
      (node (ref "TP3") (pin "TP") (pinfunction "TP_TP") (pintype "input"))
      (node (ref "U4") (pin "2") (pinfunction "CELL_2") (pintype "power_in"))
      (node (ref "U4") (pin "3") (pinfunction "VDD_3") (pintype "power_in"))
    )
    (net (code "55") (name "VBUS") (class "Default")
      (node (ref "C1_BAT") (pin "1") (pinfunction "1_1") (pintype "passive"))
      (node (ref "C4_USB") (pin "1") (pinfunction "1_1") (pintype "passive"))
      (node (ref "C5_USB") (pin "1") (pinfunction "1_1") (pintype "passive"))
      (node (ref "CHG_LED") (pin "A") (pinfunction "A_A") (pintype "passive"))
      (node (ref "D1") (pin "5") (pinfunction "VBUS_5") (pintype "bidirectional"))
      (node (ref "D2") (pin "1") (pinfunction "ANODE_1") (pintype "bidirectional"))
      (node (ref "MCP73831") (pin "4") (pinfunction "VIN_4") (pintype "power_in"))
      (node (ref "PFMF.050.1") (pin "2") (pinfunction "2_2") (pintype "passive"))
      (node (ref "Q1") (pin "2") (pinfunction "G_2") (pintype "bidirectional"))
      (node (ref "R1_PWRUSB") (pin "2") (pinfunction "2_2") (pintype "passive"))
      (node (ref "TP14") (pin "TP") (pinfunction "TP_TP") (pintype "input"))
    )
    (net (code "56") (name "VRTC") (class "Default")
      (node (ref "C10_SUPERCAP") (pin "2") (pinfunction "2_2") (pintype "passive"))
      (node (ref "C8") (pin "1") (pinfunction "1_1") (pintype "passive"))
      (node (ref "R_CAPACITOR") (pin "1") (pinfunction "1_1") (pintype "passive"))
      (node (ref "U3") (pin "14") (pinfunction "VBAT_14") (pintype "power_in"))
    )
    (net (code "57") (name "VUSB") (class "Default")
      (node (ref "J2") (pin "A4") (pinfunction "A4_A4") (pintype "bidirectional"))
      (node (ref "J2") (pin "A9") (pinfunction "A9_A9") (pintype "bidirectional"))
      (node (ref "J2") (pin "B4") (pinfunction "B4_B4") (pintype "bidirectional"))
      (node (ref "J2") (pin "B9") (pinfunction "B9_B9") (pintype "bidirectional"))
      (node (ref "PFMF.050.1") (pin "1") (pinfunction "1_1") (pintype "passive"))
    )
    (net (code "58") (name "unconnected-(IC1-NC-Pad4)") (class "Default")
      (node (ref "IC1") (pin "4") (pinfunction "NC_4") (pintype "no_connect"))
    )
    (net (code "59") (name "unconnected-(IC4-NC-Pad4)") (class "Default")
      (node (ref "IC4") (pin "4") (pinfunction "NC_4") (pintype "no_connect"))
    )
    (net (code "60") (name "unconnected-(J1-Pad1)") (class "Default")
      (node (ref "J1") (pin "1") (pinfunction "1_1") (pintype "bidirectional"))
    )
    (net (code "61") (name "unconnected-(J1-Pad6)") (class "Default")
      (node (ref "J1") (pin "6") (pinfunction "6_6") (pintype "bidirectional"))
    )
    (net (code "62") (name "unconnected-(J1-Pad7)") (class "Default")
      (node (ref "J1") (pin "7") (pinfunction "7_7") (pintype "bidirectional"))
    )
    (net (code "63") (name "unconnected-(J2-PadA8)") (class "Default")
      (node (ref "J2") (pin "A8") (pinfunction "A8_A8") (pintype "bidirectional"))
    )
    (net (code "64") (name "unconnected-(J2-PadB8)") (class "Default")
      (node (ref "J2") (pin "B8") (pinfunction "B8_B8") (pintype "bidirectional"))
    )
    (net (code "65") (name "unconnected-(J4-DAT1-PadP8)") (class "Default")
      (node (ref "J4") (pin "P8") (pinfunction "DAT1_P8") (pintype "bidirectional"))
    )
    (net (code "66") (name "unconnected-(J4-DAT2-PadP1)") (class "Default")
      (node (ref "J4") (pin "P1") (pinfunction "DAT2_P1") (pintype "bidirectional"))
    )
    (net (code "67") (name "unconnected-(J4-DETECTION_1-PadS1)") (class "Default")
      (node (ref "J4") (pin "S1") (pinfunction "DETECTION_1_S1") (pintype "bidirectional"))
    )
    (net (code "68") (name "unconnected-(J4-DETECTION_2-PadS2)") (class "Default")
      (node (ref "J4") (pin "S2") (pinfunction "DETECTION_2_S2") (pintype "bidirectional"))
    )
    (net (code "69") (name "unconnected-(U2-NC-Pad22)") (class "Default")
      (node (ref "U2") (pin "22") (pinfunction "NC_22") (pintype "no_connect"))
    )
    (net (code "70") (name "unconnected-(U4-~{ALERT}-Pad5)") (class "Default")
      (node (ref "U4") (pin "5") (pinfunction "~{ALERT}_5") (pintype "output"))
    )
  )
)
